# input.net
KiCad netlist of a schematic drawn in EAGLE
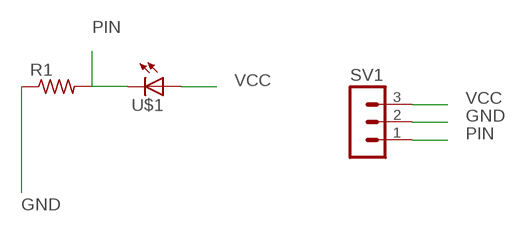
[diagram p0: schematic, sheet 1]

(export (version "E")
  (design (tool "Eeschema 10.0.6"))
  (components
    (comp (ref "R1")
      (value "RESISTOR1206")
      (footprint "eagle-import:1206")
      (libsource (lib "eagle-import") (part "RESISTOR1206"))
    )
    (comp (ref "SV1")
      (value "MA03-1")
      (footprint "eagle-import:MA03-1")
      (libsource (lib "eagle-import") (part "MA03-1"))
    )
    (comp (ref "U$1")
      (value "LED5MM")
      (footprint "eagle-import:5MM")
      (libsource (lib "eagle-import") (part "LED5MM"))
    )
  )
  (nets
    (net (code "1") (name "/GND") (class "Default")
      (node (ref "R1") (pin "1") (pinfunction "1_1") (pintype "passive"))
      (node (ref "SV1") (pin "2") (pinfunction "2_2") (pintype "passive"))
    )
    (net (code "2") (name "/PIN") (class "Default")
      (node (ref "R1") (pin "2") (pinfunction "2_2") (pintype "passive"))
      (node (ref "SV1") (pin "1") (pinfunction "1_1") (pintype "passive"))
      (node (ref "U$1") (pin "OUT") (pinfunction "C_OUT") (pintype "passive"))
    )
    (net (code "3") (name "/VCC") (class "Default")
      (node (ref "SV1") (pin "3") (pinfunction "3_3") (pintype "passive"))
      (node (ref "U$1") (pin "IN") (pinfunction "A_IN") (pintype "passive"))
    )
  )
)
